# PCB_Project.net
KiCad netlist of a schematic drawn in Altium Designer
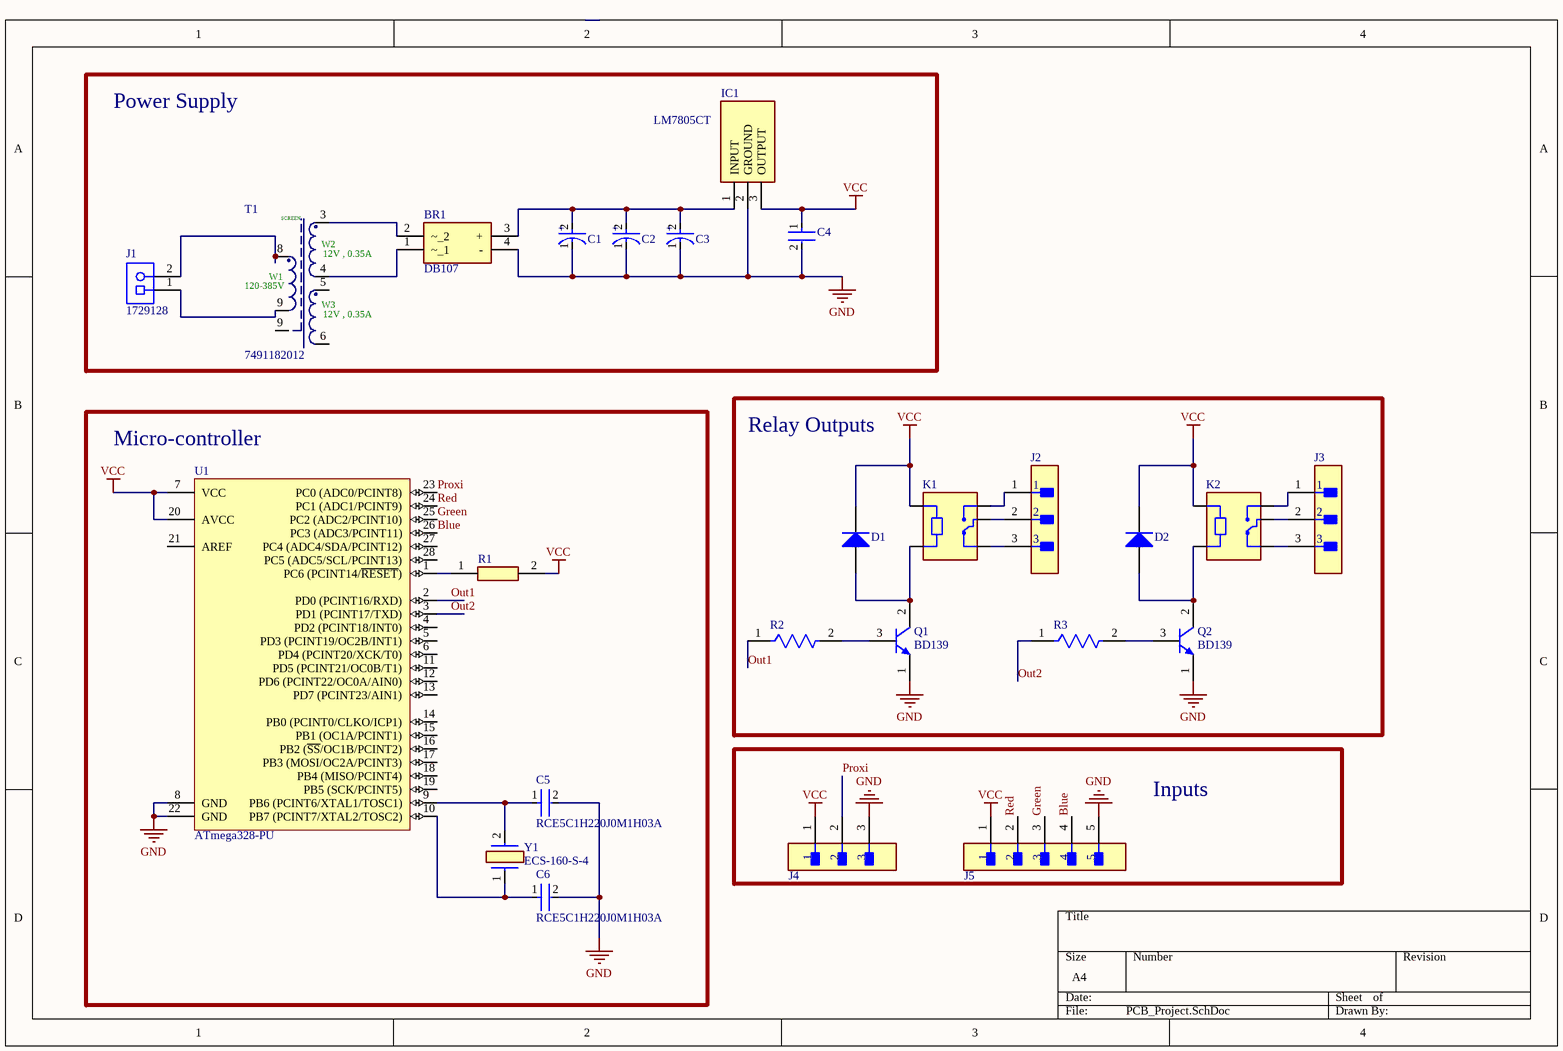
[diagram p0: PCB_Project.SchDoc]

(export (version "E")
  (design (tool "Eeschema 10.0.6"))
  (components
    (comp (ref "BR1")
      (value "DB107")
      (footprint "SamacSys:DIP825W50P510L830H340Q4N")
      (description "Bridge Rectifier")
      (fields (field (name "MOUSER PART NUMBER") "583-DB107"))
      (libsource (lib "*") (part "DB107"))
    )
    (comp (ref "C1")
      (value "EEUTA1E101")
      (footprint "FP-RAD-TH-D_8_0_5-L_11_5-MFG")
      (description "Aluminum Electrolytic Capacitors (Radial Lead Type) AEC-Q200 Qualified 100uF ±20% 25V")
      (fields (field (name "VOLTAGE") "25V") (field (name "TOLERANCE") "20%"))
      (libsource (lib "Altium Content Vault") (part "203bc49f2ac43e59fd269a8c329ed05"))
    )
    (comp (ref "C2")
      (value "ECA2CHG470B")
      (footprint "FP-RAD-TH-D_12_5_0_5-L_20-MFG")
      (description "Aluminum Electrolytic Capacitors (Radial Lead Type) 47uF ±20% 160V")
      (fields (field (name "TOLERANCE") "20%"))
      (libsource (lib "Altium Content Vault") (part "a00bbbee19879c290e62620ae7e47b1"))
    )
    (comp (ref "C3")
      (value "ECA2AM100")
      (footprint "FP-RAD-TH-D_5_0_5-L_11_1-MFG")
      (description "Aluminum Electrolytic Capacitors (Radial Lead Type) 10uF ±20% 100V")
      (fields (field (name "VOLTAGE") "100V") (field (name "TOLERANCE") "20%"))
      (libsource (lib "Altium Content Vault") (part "a00bbbee19879c290e62620ae7e47b1"))
    )
    (comp (ref "C4")
      (value "RCER72A104K1K1H03B")
      (footprint "FP-RCE1K1-2_5-MFG")
      (description "Cap Ceramic Monolithic 100nF 100V 10% Thru-Hole Bulk")
      (fields (field (name "TOLERANCE") "10%"))
      (libsource (lib "Altium Content Vault") (part "02cd4be3c70576c341d710602a673aa"))
    )
    (comp (ref "C5")
      (value "RCE5C1H220J0M1H03A")
      (footprint "FP-RCE0K1-MFG")
      (description "Cap Ceramic 22pF 50V C0G ±5% Radial 5mm +125°C Automotive Bulk")
      (fields (field (name "TOLERANCE") "5%"))
      (libsource (lib "Altium Content Vault") (part "b4654b650e69147ec39a6b967a45e02"))
    )
    (comp (ref "C6")
      (value "RCE5C1H220J0M1H03A")
      (footprint "FP-RCE0K1-MFG")
      (description "Cap Ceramic 22pF 50V C0G ±5% Radial 5mm +125°C Automotive Bulk")
      (fields (field (name "TOLERANCE") "5%"))
      (libsource (lib "Altium Content Vault") (part "b4654b650e69147ec39a6b967a45e02"))
    )
    (comp (ref "D1")
      (value "1N4001-T")
      (footprint "DIOD-DO-41-P-2_V")
      (description "1.0 A Rectifier, 15 pF, 50 V, -65 to 150 degC, 2-Pin DO-41 Plastic, RoHS, Tape and Reel")
      (fields (field (name "MANUFACTURER") "Diodes Inc"))
      (libsource (lib "Altium Content Vault") (part "DIOD-D-A1K2-2"))
    )
    (comp (ref "D2")
      (value "1N4001-T")
      (footprint "DIOD-DO-41-P-2_V")
      (description "1.0 A Rectifier, 15 pF, 50 V, -65 to 150 degC, 2-Pin DO-41 Plastic, RoHS, Tape and Reel")
      (fields (field (name "MANUFACTURER") "Diodes Inc"))
      (libsource (lib "Altium Content Vault") (part "DIOD-D-A1K2-2"))
    )
    (comp (ref "IC1")
      (value "LM7805CT")
      (footprint "SamacSys:TO254P470X1028X1955-3P")
      (description "Integrated Circuit")
      (fields (field (name "MOUSER PART NUMBER") "926-LM7805CT"))
      (libsource (lib "*") (part "LM7805CT"))
    )
    (comp (ref "J1")
      (value "1729128")
      (footprint "PHOE-1729128-2_V")
      (description "PCB Terminal Block, 13.5 A, 400 V, 2-Pin THD, RoHS, Bulk")
      (fields (field (name "MANUFACTURER") "Phoenix Contact"))
      (libsource (lib "Altium Content Vault") (part "CN-2P-F-R2"))
    )
    (comp (ref "J2")
      (value "B3B-XH-A(LF)(SN)")
      (footprint "FP-B3B-XH-A_LF_SN-MFG")
      (description "CONN HEADER VERT 3POS 2.5MM")
      (libsource (lib "Altium Content Vault") (part "0d3f023dd272f625e17a2be33dea85f"))
    )
    (comp (ref "J3")
      (value "B3B-XH-A(LF)(SN)")
      (footprint "FP-B3B-XH-A_LF_SN-MFG")
      (description "CONN HEADER VERT 3POS 2.5MM")
      (libsource (lib "Altium Content Vault") (part "0d3f023dd272f625e17a2be33dea85f"))
    )
    (comp (ref "J4")
      (value "B3B-XH-A(LF)(SN)")
      (footprint "FP-B3B-XH-A_LF_SN-MFG")
      (description "CONN HEADER VERT 3POS 2.5MM")
      (libsource (lib "") (part "0d3f023dd272f625e17a2be33dea85f_1"))
    )
    (comp (ref "J5")
      (value "B5B-EH-A(LF)(SN)")
      (footprint "FP-B5B-EH-A_LF_SN-MFG")
      (description "CONN HEADER VERT 5POS 2.5MM")
      (libsource (lib "Altium Content Vault") (part "bf93c07fd2649a848d0ec8585582aab"))
    )
    (comp (ref "K1")
      (value "SRD-05VDC-SL-C")
      (footprint "RELAY_SRD-05VDC-SL-C")
      (fields (field (name "MF") "Songle Relay"))
      (libsource (lib "SRD-05VDC-SL-C") (part "SRD-05VDC-SL-C"))
    )
    (comp (ref "K2")
      (value "SRD-05VDC-SL-C")
      (footprint "RELAY_SRD-05VDC-SL-C")
      (fields (field (name "MF") "Songle Relay"))
      (libsource (lib "SRD-05VDC-SL-C") (part "SRD-05VDC-SL-C"))
    )
    (comp (ref "Q1")
      (value "BD139")
      (footprint "ONSC-TO-225-3-77-09")
      (description "Plastic Medium-Power Silicon NPN Transistor, 3-Pin TO-225, Bulk Box")
      (fields (field (name "MANUFACTURER") "On Semiconductor"))
      (libsource (lib "Altium Content Vault") (part "ONSC-NPN-E1C2B3-3"))
    )
    (comp (ref "Q2")
      (value "BD139")
      (footprint "ONSC-TO-225-3-77-09")
      (description "Plastic Medium-Power Silicon NPN Transistor, 3-Pin TO-225, Bulk Box")
      (fields (field (name "MANUFACTURER") "On Semiconductor"))
      (libsource (lib "Altium Content Vault") (part "ONSC-NPN-E1C2B3-3"))
    )
    (comp (ref "R1")
      (value "PR02000201001JR500")
      (footprint "SamacSys:RESAD2760W63L1200D390")
      (description "Resistor")
      (fields (field (name "MOUSER PART NUMBER") "594-5083NW1K000J"))
      (libsource (lib "*") (part "PR02000201001JR500"))
    )
    (comp (ref "R2")
      (value "MFR-25FBF52-1K18")
      (footprint "FP-MFR-25-MFG")
      (description "RES 1.18K OHM 1/4W 1% AXIAL")
      (fields (field (name "MANUFACTURER") "Yageo") (field (name "TOLERANCE") "1%"))
      (libsource (lib "Altium Content Vault") (part "1029c3af85768c4190bb7ad29bc67b5"))
    )
    (comp (ref "R3")
      (value "MFR-25FBF52-1K18")
      (footprint "FP-MFR-25-MFG")
      (description "RES 1.18K OHM 1/4W 1% AXIAL")
      (fields (field (name "MANUFACTURER") "Yageo") (field (name "TOLERANCE") "1%"))
      (libsource (lib "Altium Content Vault") (part "1029c3af85768c4190bb7ad29bc67b5"))
    )
    (comp (ref "T1")
      (value "7491182012")
      (footprint "EE16_7_4 (E16)")
      (description "Off-Line Transformer WE-UNIT , L=0.9mH")
      (fields (field (name "MANUFACTURER") "Wuerth Elektronik"))
      (libsource (lib "Altium Content Vault") (part "WE-7491182012"))
    )
    (comp (ref "U1")
      (value "ATmega328-PU")
      (footprint "28P3")
      (libsource (lib "Altium Content Vault") (part "MC-8B-ATM48-IL28"))
    )
    (comp (ref "Y1")
      (value "ECS-160-S-4")
      (footprint "SamacSys:ECS160S4")
      (description "Crystal or Oscillator")
      (fields (field (name "MOUSER PART NUMBER") "520-HCU1600-S"))
      (libsource (lib "*") (part "ECS-160-S-4"))
    )
  )
  (nets
    (net (code "1") (name "/Blue") (class "Default")
      (node (ref "J5") (pin "4") (pinfunction "4_4") (pintype "passive"))
      (node (ref "U1") (pin "26") (pinfunction "PC3_(ADC3/PCINT11)_26") (pintype "bidirectional"))
    )
    (net (code "2") (name "/Green") (class "Default")
      (node (ref "J5") (pin "3") (pinfunction "3_3") (pintype "passive"))
      (node (ref "U1") (pin "25") (pinfunction "PC2_(ADC2/PCINT10)_25") (pintype "bidirectional"))
    )
    (net (code "3") (name "/Out1") (class "Default")
      (node (ref "R2") (pin "1") (pinfunction "1_1") (pintype "passive"))
      (node (ref "U1") (pin "2") (pinfunction "PD0_(PCINT16/RXD)_2") (pintype "bidirectional"))
    )
    (net (code "4") (name "/Out2") (class "Default")
      (node (ref "R3") (pin "1") (pinfunction "1_1") (pintype "passive"))
      (node (ref "U1") (pin "3") (pinfunction "PD1_(PCINT17/TXD)_3") (pintype "bidirectional"))
    )
    (net (code "5") (name "/Proxi") (class "Default")
      (node (ref "J4") (pin "2") (pinfunction "2_2") (pintype "passive"))
      (node (ref "U1") (pin "23") (pinfunction "PC0_(ADC0/PCINT8)_23") (pintype "bidirectional"))
    )
    (net (code "6") (name "/Red") (class "Default")
      (node (ref "J5") (pin "2") (pinfunction "2_2") (pintype "passive"))
      (node (ref "U1") (pin "24") (pinfunction "PC1_(ADC1/PCINT9)_24") (pintype "bidirectional"))
    )
    (net (code "7") (name "GND") (class "Default")
      (node (ref "BR1") (pin "4") (pinfunction "-_4") (pintype "passive"))
      (node (ref "C1") (pin "1") (pinfunction "C_1") (pintype "passive"))
      (node (ref "C2") (pin "1") (pinfunction "C_1") (pintype "passive"))
      (node (ref "C3") (pin "1") (pinfunction "C_1") (pintype "passive"))
      (node (ref "C4") (pin "2") (pinfunction "2_2") (pintype "passive"))
      (node (ref "C5") (pin "2") (pinfunction "2_2") (pintype "passive"))
      (node (ref "C6") (pin "2") (pinfunction "2_2") (pintype "passive"))
      (node (ref "IC1") (pin "2") (pinfunction "GROUND_2") (pintype "passive"))
      (node (ref "J4") (pin "3") (pinfunction "3_3") (pintype "passive"))
      (node (ref "J5") (pin "5") (pinfunction "5_5") (pintype "passive"))
      (node (ref "Q1") (pin "1") (pinfunction "E_1") (pintype "passive"))
      (node (ref "Q2") (pin "1") (pinfunction "E_1") (pintype "passive"))
      (node (ref "U1") (pin "22") (pinfunction "GND_22") (pintype "power_in"))
      (node (ref "U1") (pin "8") (pinfunction "GND_8") (pintype "power_in"))
    )
    (net (code "8") (name "Net-(BR1-+)") (class "Default")
      (node (ref "BR1") (pin "3") (pinfunction "+_3") (pintype "passive"))
      (node (ref "C1") (pin "2") (pinfunction "A_2") (pintype "passive"))
      (node (ref "C2") (pin "2") (pinfunction "A_2") (pintype "passive"))
      (node (ref "C3") (pin "2") (pinfunction "A_2") (pintype "passive"))
      (node (ref "IC1") (pin "1") (pinfunction "INPUT_1") (pintype "passive"))
    )
    (net (code "9") (name "Net-(BR1-~_1)") (class "Default")
      (node (ref "BR1") (pin "1") (pinfunction "~_1_1") (pintype "passive"))
      (node (ref "T1") (pin "4") (pinfunction "4_4") (pintype "passive"))
    )
    (net (code "10") (name "Net-(BR1-~_2)") (class "Default")
      (node (ref "BR1") (pin "2") (pinfunction "~_2_2") (pintype "passive"))
      (node (ref "T1") (pin "3") (pinfunction "3_3") (pintype "passive"))
    )
    (net (code "11") (name "Net-(D1-A)") (class "Default")
      (node (ref "D1") (pin "1") (pinfunction "A_1") (pintype "passive"))
      (node (ref "K1") (pin "A2") (pinfunction "A2_A2") (pintype "passive"))
      (node (ref "Q1") (pin "2") (pinfunction "C_2") (pintype "passive"))
    )
    (net (code "12") (name "Net-(D2-A)") (class "Default")
      (node (ref "D2") (pin "1") (pinfunction "A_1") (pintype "passive"))
      (node (ref "K2") (pin "A2") (pinfunction "A2_A2") (pintype "passive"))
      (node (ref "Q2") (pin "2") (pinfunction "C_2") (pintype "passive"))
    )
    (net (code "13") (name "Net-(J1-Pad1)") (class "Default")
      (node (ref "J1") (pin "1") (pinfunction "1_1") (pintype "passive"))
      (node (ref "T1") (pin "9") (pinfunction "9_9") (pintype "passive"))
    )
    (net (code "14") (name "Net-(J1-Pad2)") (class "Default")
      (node (ref "J1") (pin "2") (pinfunction "2_2") (pintype "passive"))
      (node (ref "T1") (pin "8") (pinfunction "8_8") (pintype "passive"))
    )
    (net (code "15") (name "Net-(J2-Pad1)") (class "Default")
      (node (ref "J2") (pin "1") (pinfunction "1_1") (pintype "passive"))
      (node (ref "K1") (pin "NO") (pinfunction "NO_NO") (pintype "passive"))
    )
    (net (code "16") (name "Net-(J2-Pad2)") (class "Default")
      (node (ref "J2") (pin "2") (pinfunction "2_2") (pintype "passive"))
      (node (ref "K1") (pin "COM") (pinfunction "COM_COM") (pintype "passive"))
    )
    (net (code "17") (name "Net-(J2-Pad3)") (class "Default")
      (node (ref "J2") (pin "3") (pinfunction "3_3") (pintype "passive"))
      (node (ref "K1") (pin "NC") (pinfunction "NC_NC") (pintype "passive"))
    )
    (net (code "18") (name "Net-(J3-Pad1)") (class "Default")
      (node (ref "J3") (pin "1") (pinfunction "1_1") (pintype "passive"))
      (node (ref "K2") (pin "NO") (pinfunction "NO_NO") (pintype "passive"))
    )
    (net (code "19") (name "Net-(J3-Pad2)") (class "Default")
      (node (ref "J3") (pin "2") (pinfunction "2_2") (pintype "passive"))
      (node (ref "K2") (pin "COM") (pinfunction "COM_COM") (pintype "passive"))
    )
    (net (code "20") (name "Net-(J3-Pad3)") (class "Default")
      (node (ref "J3") (pin "3") (pinfunction "3_3") (pintype "passive"))
      (node (ref "K2") (pin "NC") (pinfunction "NC_NC") (pintype "passive"))
    )
    (net (code "21") (name "Net-(Q1-B)") (class "Default")
      (node (ref "Q1") (pin "3") (pinfunction "B_3") (pintype "passive"))
      (node (ref "R2") (pin "2") (pinfunction "2_2") (pintype "passive"))
    )
    (net (code "22") (name "Net-(Q2-B)") (class "Default")
      (node (ref "Q2") (pin "3") (pinfunction "B_3") (pintype "passive"))
      (node (ref "R3") (pin "2") (pinfunction "2_2") (pintype "passive"))
    )
    (net (code "23") (name "Net-(U1-PB6_(PCINT6{slash}XTAL1{slash}TOSC1))") (class "Default")
      (node (ref "C5") (pin "1") (pinfunction "1_1") (pintype "passive"))
      (node (ref "U1") (pin "9") (pinfunction "PB6_(PCINT6/XTAL1/TOSC1)_9") (pintype "bidirectional"))
      (node (ref "Y1") (pin "2") (pinfunction "2_2") (pintype "passive"))
    )
    (net (code "24") (name "Net-(U1-PB7_(PCINT7{slash}XTAL2{slash}TOSC2))") (class "Default")
      (node (ref "C6") (pin "1") (pinfunction "1_1") (pintype "passive"))
      (node (ref "U1") (pin "10") (pinfunction "PB7_(PCINT7/XTAL2/TOSC2)_10") (pintype "bidirectional"))
      (node (ref "Y1") (pin "1") (pinfunction "1_1") (pintype "passive"))
    )
    (net (code "25") (name "Net-(U1-PC6_(PCINT14{slash}~{RESET}))") (class "Default")
      (node (ref "R1") (pin "1") (pinfunction "1_1") (pintype "passive"))
      (node (ref "U1") (pin "1") (pinfunction "PC6_(PCINT14/~{RESET})_1") (pintype "bidirectional"))
    )
    (net (code "26") (name "VCC") (class "Default")
      (node (ref "C4") (pin "1") (pinfunction "1_1") (pintype "passive"))
      (node (ref "D1") (pin "2") (pinfunction "K_2") (pintype "passive"))
      (node (ref "D2") (pin "2") (pinfunction "K_2") (pintype "passive"))
      (node (ref "IC1") (pin "3") (pinfunction "OUTPUT_3") (pintype "passive"))
      (node (ref "J4") (pin "1") (pinfunction "1_1") (pintype "passive"))
      (node (ref "J5") (pin "1") (pinfunction "1_1") (pintype "passive"))
      (node (ref "K1") (pin "A1") (pinfunction "A1_A1") (pintype "passive"))
      (node (ref "K2") (pin "A1") (pinfunction "A1_A1") (pintype "passive"))
      (node (ref "R1") (pin "2") (pinfunction "2_2") (pintype "passive"))
      (node (ref "U1") (pin "20") (pinfunction "AVCC_20") (pintype "power_in"))
      (node (ref "U1") (pin "7") (pinfunction "VCC_7") (pintype "power_in"))
    )
    (net (code "27") (name "unconnected-(T1-Pad5)") (class "Default")
      (node (ref "T1") (pin "5") (pinfunction "5_5") (pintype "passive"))
    )
    (net (code "28") (name "unconnected-(T1-Pad6)") (class "Default")
      (node (ref "T1") (pin "6") (pinfunction "6_6") (pintype "passive"))
    )
    (net (code "29") (name "unconnected-(T1-Pad9)") (class "Default")
      (node (ref "T1") (pin "9") (pinfunction "9_9") (pintype "passive"))
    )
    (net (code "30") (name "unconnected-(U1-AREF-Pad21)") (class "Default")
      (node (ref "U1") (pin "21") (pinfunction "AREF_21") (pintype "power_in"))
    )
    (net (code "31") (name "unconnected-(U1-PB0_(PCINT0{slash}CLKO{slash}ICP1)-Pad14)") (class "Default")
      (node (ref "U1") (pin "14") (pinfunction "PB0_(PCINT0/CLKO/ICP1)_14") (pintype "bidirectional"))
    )
    (net (code "32") (name "unconnected-(U1-PB1_(OC1A{slash}PCINT1)-Pad15)") (class "Default")
      (node (ref "U1") (pin "15") (pinfunction "PB1_(OC1A/PCINT1)_15") (pintype "bidirectional"))
    )
    (net (code "33") (name "unconnected-(U1-PB2_(~{SS}{slash}OC1B{slash}PCINT2)-Pad16)") (class "Default")
      (node (ref "U1") (pin "16") (pinfunction "PB2_(~{SS}/OC1B/PCINT2)_16") (pintype "bidirectional"))
    )
    (net (code "34") (name "unconnected-(U1-PB3_(MOSI{slash}OC2A{slash}PCINT3)-Pad17)") (class "Default")
      (node (ref "U1") (pin "17") (pinfunction "PB3_(MOSI/OC2A/PCINT3)_17") (pintype "bidirectional"))
    )
    (net (code "35") (name "unconnected-(U1-PB4_(MISO{slash}PCINT4)-Pad18)") (class "Default")
      (node (ref "U1") (pin "18") (pinfunction "PB4_(MISO/PCINT4)_18") (pintype "bidirectional"))
    )
    (net (code "36") (name "unconnected-(U1-PB5_(SCK{slash}PCINT5)-Pad19)") (class "Default")
      (node (ref "U1") (pin "19") (pinfunction "PB5_(SCK/PCINT5)_19") (pintype "bidirectional"))
    )
    (net (code "37") (name "unconnected-(U1-PC4_(ADC4{slash}SDA{slash}PCINT12)-Pad27)") (class "Default")
      (node (ref "U1") (pin "27") (pinfunction "PC4_(ADC4/SDA/PCINT12)_27") (pintype "bidirectional"))
    )
    (net (code "38") (name "unconnected-(U1-PC5_(ADC5{slash}SCL{slash}PCINT13)-Pad28)") (class "Default")
      (node (ref "U1") (pin "28") (pinfunction "PC5_(ADC5/SCL/PCINT13)_28") (pintype "bidirectional"))
    )
    (net (code "39") (name "unconnected-(U1-PD2_(PCINT18{slash}INT0)-Pad4)") (class "Default")
      (node (ref "U1") (pin "4") (pinfunction "PD2_(PCINT18/INT0)_4") (pintype "bidirectional"))
    )
    (net (code "40") (name "unconnected-(U1-PD3_(PCINT19{slash}OC2B{slash}INT1)-Pad5)") (class "Default")
      (node (ref "U1") (pin "5") (pinfunction "PD3_(PCINT19/OC2B/INT1)_5") (pintype "bidirectional"))
    )
    (net (code "41") (name "unconnected-(U1-PD4_(PCINT20{slash}XCK{slash}T0)-Pad6)") (class "Default")
      (node (ref "U1") (pin "6") (pinfunction "PD4_(PCINT20/XCK/T0)_6") (pintype "bidirectional"))
    )
    (net (code "42") (name "unconnected-(U1-PD5_(PCINT21{slash}OC0B{slash}T1)-Pad11)") (class "Default")
      (node (ref "U1") (pin "11") (pinfunction "PD5_(PCINT21/OC0B/T1)_11") (pintype "bidirectional"))
    )
    (net (code "43") (name "unconnected-(U1-PD6_(PCINT22{slash}OC0A{slash}AIN0)-Pad12)") (class "Default")
      (node (ref "U1") (pin "12") (pinfunction "PD6_(PCINT22/OC0A/AIN0)_12") (pintype "bidirectional"))
    )
    (net (code "44") (name "unconnected-(U1-PD7_(PCINT23{slash}AIN1)-Pad13)") (class "Default")
      (node (ref "U1") (pin "13") (pinfunction "PD7_(PCINT23/AIN1)_13") (pintype "bidirectional"))
    )
  )
)
